# SAM_E54_Xplained_Pro_triple_input_power_.net
KiCad netlist of a schematic drawn in Altium Designer
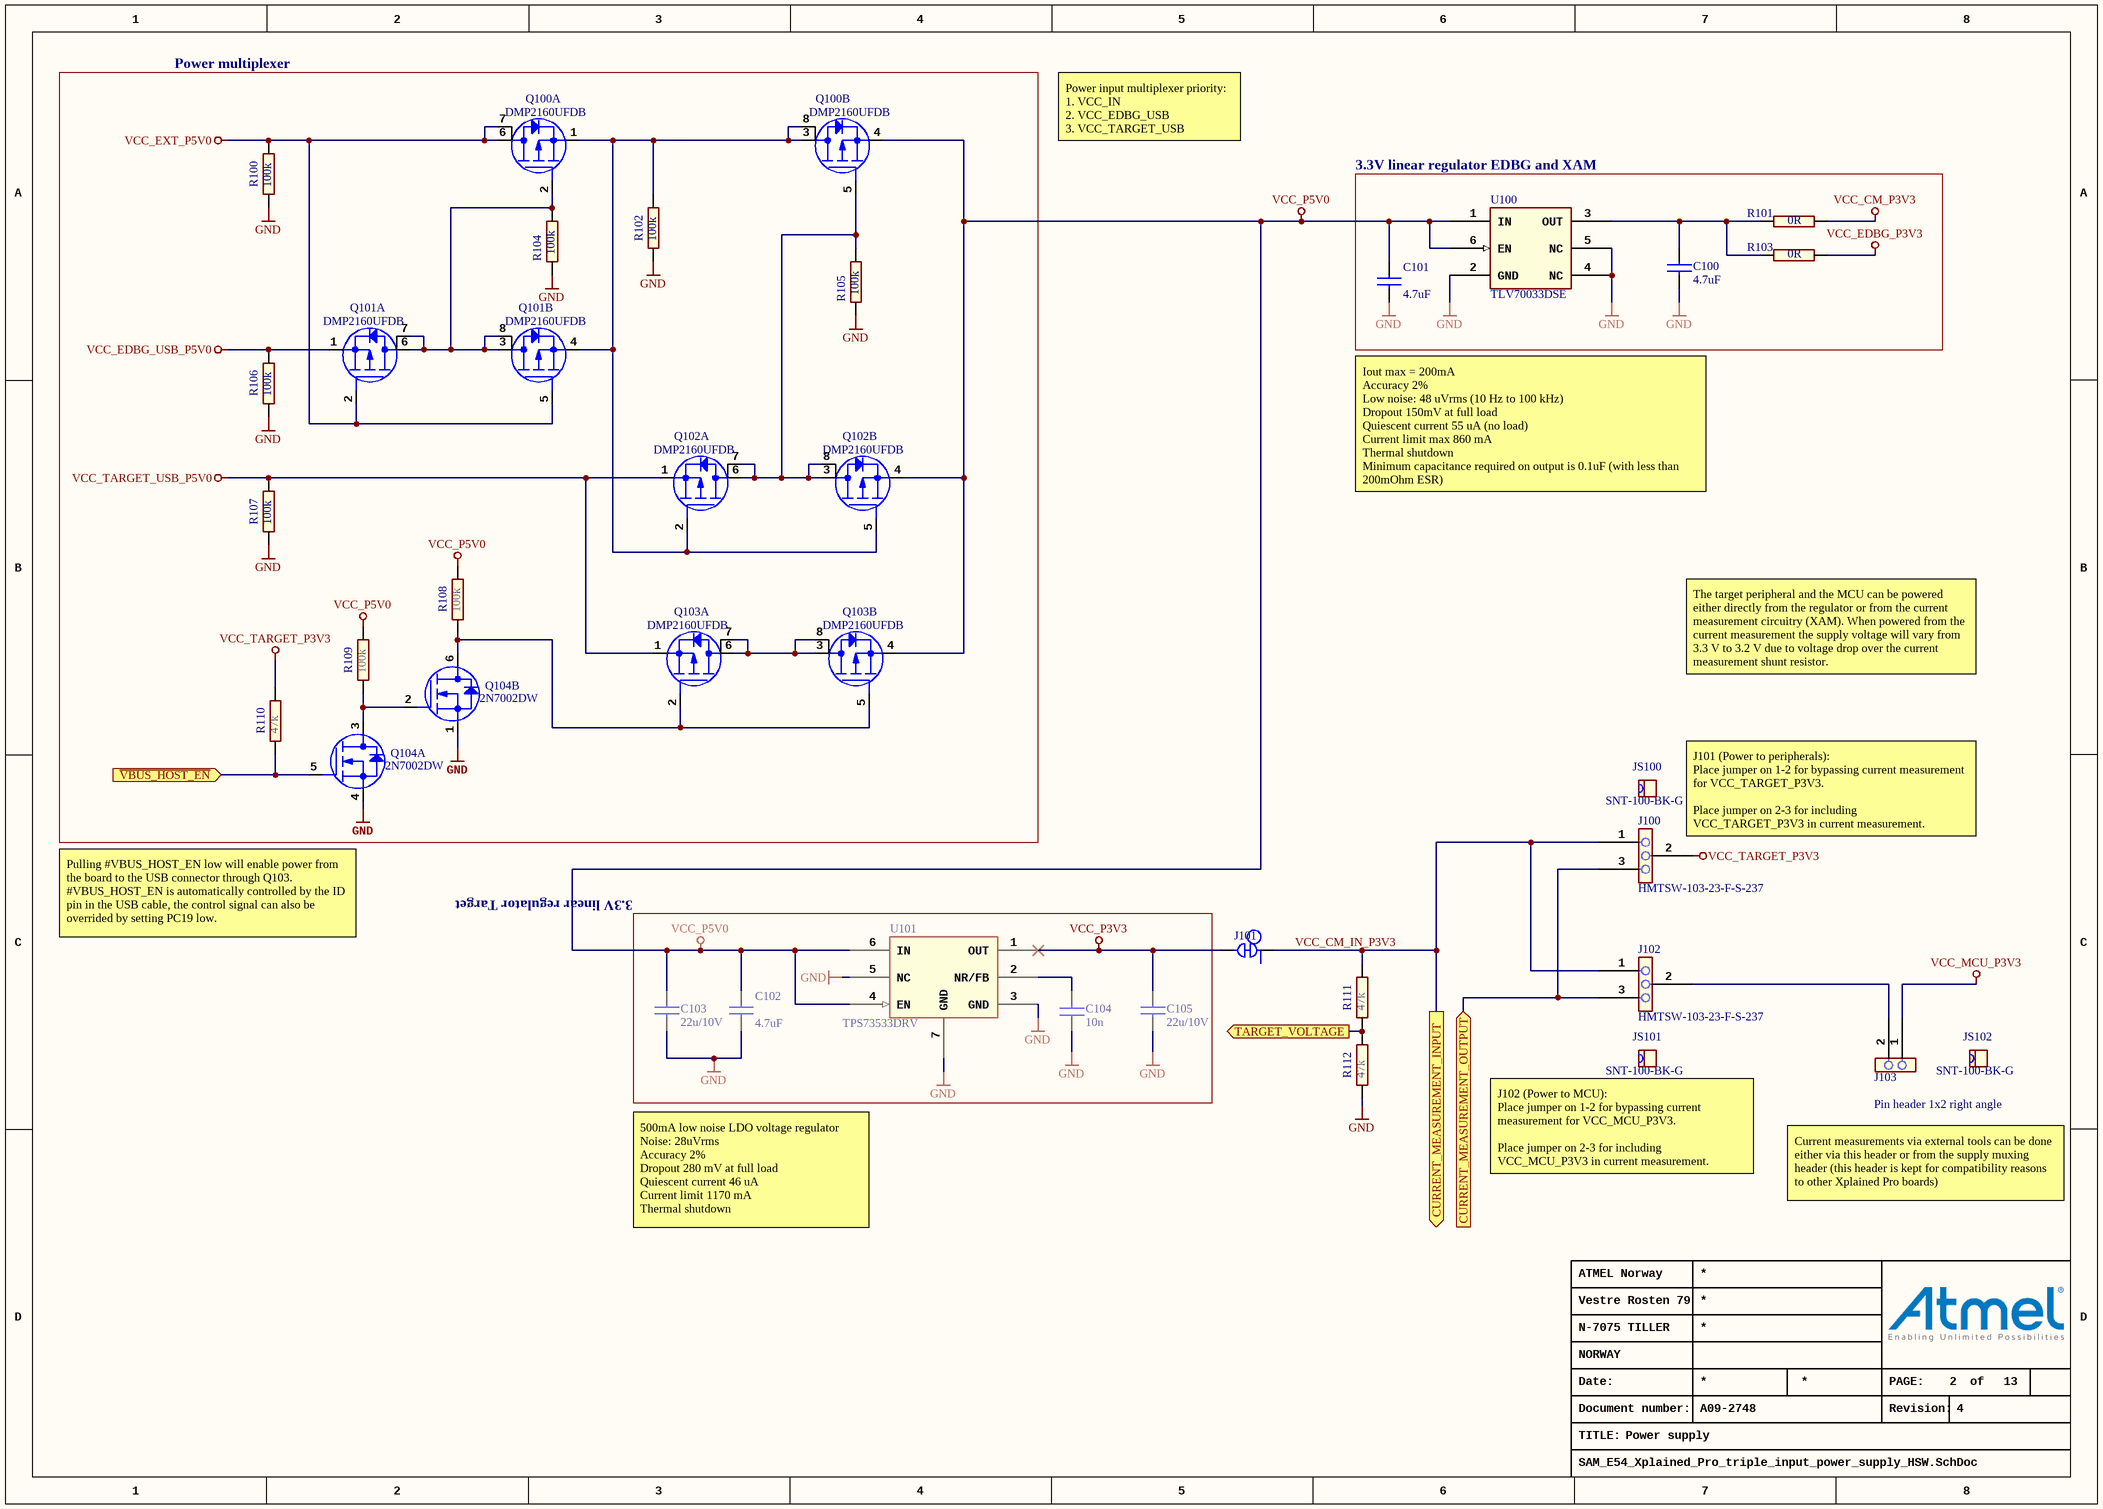
[diagram p0: SAM_E54_Xplained_Pro_triple_input_power_supply_HSW.SchDoc]

(export (version "E")
  (design (tool "Eeschema 10.0.6"))
  (components
    (comp (ref "C100")
      (value "4.7uF")
      (footprint "AP1-00117")
      (description "Ceramic capacitor, SMD 0603, X5R, 10V, 10% (de31036)")
      (fields (field (name "TOLERANCE") "10%") (field (name "MANUFACTURER") "WALSIN Technology Corporation"))
      (libsource (lib "AltiumDbLib") (part "CAP-NONPOL"))
    )
    (comp (ref "C101")
      (value "4.7uF")
      (footprint "AP1-00117")
      (description "Ceramic capacitor, SMD 0603, X5R, 10V, 10% (de31036)")
      (fields (field (name "TOLERANCE") "10%") (field (name "MANUFACTURER") "WALSIN Technology Corporation"))
      (libsource (lib "AltiumDbLib") (part "CAP-NONPOL"))
    )
    (comp (ref "C102")
      (value "4.7uF")
      (footprint "AP1-00117")
      (description "Ceramic capacitor, SMD 0603, X5R, 10V, 10% (de31036)")
      (fields (field (name "TOLERANCE") "10%") (field (name "MANUFACTURER") "WALSIN Technology Corporation"))
      (libsource (lib "AltiumDbLib") (part "CAP-NONPOL"))
    )
    (comp (ref "C103")
      (value "22u/10V")
      (footprint "AP1-00117")
      (description "Ceramic capacitor, SMD 0603, X5R,10V, Â±20%")
      (fields (field (name "MANUFACTURER") "Murata") (field (name "MPN") "GRM188R61A226ME15D"))
      (libsource (lib "AltiumDbLib") (part "CAP-NONPOL"))
    )
    (comp (ref "C104")
      (value "10n")
      (footprint "AP1-00053")
      (description "Ceramic capacitor, SMD 0402, X7R, 25V, +/-10%")
      (fields (field (name "TOLERANCE") "25V, +/-10%") (field (name "MANUFACTURER") "YAGEO CORP"))
      (libsource (lib "AltiumDbLib") (part "CAP-NONPOL"))
    )
    (comp (ref "C105")
      (value "22u/10V")
      (footprint "AP1-00117")
      (description "Ceramic capacitor, SMD 0603, X5R,10V, Â±20%")
      (fields (field (name "MANUFACTURER") "Murata") (field (name "MPN") "GRM188R61A226ME15D"))
      (libsource (lib "AltiumDbLib") (part "CAP-NONPOL"))
    )
    (comp (ref "J100")
      (value "HMTSW-103-23-F-S-237")
      (footprint "AP8-00745")
      (description "1x3 pin header, 2.54mm pitch, Pin-in-Paste THM, 1mm hole")
      (fields (field (name "MANUFACTURER") "SAMTEC"))
      (libsource (lib "AltiumDbLib") (part "HEADER 1x3"))
    )
    (comp (ref "J101")
      (value "~")
      (footprint "AP9-00044")
      (description "Default closed SMD strap, 0603 size")
      (libsource (lib "AltiumDbLib") (part "SMD-STRAP_CLOSED"))
    )
    (comp (ref "J102")
      (value "HMTSW-103-23-F-S-237")
      (footprint "AP8-00745")
      (description "1x3 pin header, 2.54mm pitch, Pin-in-Paste THM, 1mm hole")
      (fields (field (name "MANUFACTURER") "SAMTEC"))
      (libsource (lib "AltiumDbLib") (part "HEADER 1x3"))
    )
    (comp (ref "J103")
      (value "Pin header 1x2 right angle")
      (footprint "AP8-00367")
      (description "1x2 pin header, right angle, 2.54 mm pitch, through-hole")
      (fields (field (name "MANUFACTURER") "Pro-data International Corp") (field (name "MPN") "2213R-2G"))
      (libsource (lib "AltiumDbLib") (part "HEADER 1x2"))
    )
    (comp (ref "JS100")
      (value "SNT-100-BK-G")
      (footprint "AP8-00525")
      (description "Jumper cap for 2.54mm pinheader")
      (fields (field (name "MANUFACTURER") "SAMTEC"))
      (libsource (lib "AltiumDbLib") (part "JUMPER_CAP"))
    )
    (comp (ref "JS101")
      (value "SNT-100-BK-G")
      (footprint "AP8-00525")
      (description "Jumper cap for 2.54mm pinheader")
      (fields (field (name "MANUFACTURER") "SAMTEC"))
      (libsource (lib "AltiumDbLib") (part "JUMPER_CAP"))
    )
    (comp (ref "JS102")
      (value "SNT-100-BK-G")
      (footprint "AP8-00525")
      (description "Jumper cap for 2.54mm pinheader")
      (fields (field (name "MANUFACTURER") "SAMTEC"))
      (libsource (lib "AltiumDbLib") (part "JUMPER_CAP"))
    )
    (comp (ref "Q100")
      (value "DMP2160UFDB")
      (footprint "AP5-00047")
      (description "MOSFET 20V 3.8A DUAL P-CHAN, Rds 70 mOhms, Vgs 12V, Vds -20")
      (fields (field (name "MANUFACTURER") "Diodes Incorporated") (field (name "MPN") "DMP2160UFDB-7"))
      (libsource (lib "AltiumDbLib") (part "MOSFET_DUAL_P_S1G1D2S2G2D1D1D2"))
    )
    (comp (ref "Q101")
      (value "DMP2160UFDB")
      (footprint "AP5-00047")
      (description "MOSFET 20V 3.8A DUAL P-CHAN, Rds 70 mOhms, Vgs 12V, Vds -20")
      (fields (field (name "MANUFACTURER") "Diodes Incorporated") (field (name "MPN") "DMP2160UFDB-7"))
      (libsource (lib "AltiumDbLib") (part "MOSFET_DUAL_P_S1G1D2S2G2D1D1D2"))
    )
    (comp (ref "Q102")
      (value "DMP2160UFDB")
      (footprint "AP5-00047")
      (description "MOSFET 20V 3.8A DUAL P-CHAN, Rds 70 mOhms, Vgs 12V, Vds -20")
      (fields (field (name "MANUFACTURER") "Diodes Incorporated") (field (name "MPN") "DMP2160UFDB-7"))
      (libsource (lib "AltiumDbLib") (part "MOSFET_DUAL_P_S1G1D2S2G2D1D1D2"))
    )
    (comp (ref "Q103")
      (value "DMP2160UFDB")
      (footprint "AP5-00047")
      (description "MOSFET 20V 3.8A DUAL P-CHAN, Rds 70 mOhms, Vgs 12V, Vds -20")
      (fields (field (name "MANUFACTURER") "Diodes Incorporated") (field (name "MPN") "DMP2160UFDB-7"))
      (libsource (lib "AltiumDbLib") (part "MOSFET_DUAL_P_S1G1D2S2G2D1D1D2"))
    )
    (comp (ref "Q104")
      (value "2N7002DW")
      (footprint "AP5-00001")
      (description "Dual N-Channel MOSFET, 60V, 115mA cont,RDS(ON) < 7.5 Ohm @50mA@5V, SOT-363")
      (fields
        (field (name "MANUFACTURER") "Fairchild")
        (field (name "Comment") "Same as 2N7002 but with two MOSFETs in one package")
      )
      (libsource (lib "AltiumDbLib") (part "MOSFET_DUAL_N_S2G2D1S1G1D2"))
    )
    (comp (ref "R100")
      (value "100k")
      (footprint "AP2-00011")
      (description "Thick film resistor, SMD 0402, 1/16W, 1%")
      (fields (field (name "TOLERANCE") "1 %") (field (name "MANUFACTURER") "ASJ"))
      (libsource (lib "") (part "R2_1"))
    )
    (comp (ref "R101")
      (value "0R")
      (footprint "AP2-00011")
      (description "RES 0.0 OHM 1/16W 0402 SMD")
      (fields (field (name "TOLERANCE") "1 %") (field (name "MANUFACTURER") "(n/a)"))
      (libsource (lib "") (part "R2_3"))
    )
    (comp (ref "R102")
      (value "100k")
      (footprint "AP2-00011")
      (description "Thick film resistor, SMD 0402, 1/16W, 1%")
      (fields (field (name "TOLERANCE") "1 %") (field (name "MANUFACTURER") "ASJ"))
      (libsource (lib "") (part "R2_1"))
    )
    (comp (ref "R103")
      (value "0R")
      (footprint "AP2-00011")
      (description "RES 0.0 OHM 1/16W 0402 SMD")
      (fields (field (name "TOLERANCE") "1 %") (field (name "MANUFACTURER") "(n/a)"))
      (libsource (lib "") (part "R2_3"))
    )
    (comp (ref "R104")
      (value "100k")
      (footprint "AP2-00011")
      (description "Thick film resistor, SMD 0402, 1/16W, 1%")
      (fields (field (name "TOLERANCE") "1 %") (field (name "MANUFACTURER") "ASJ"))
      (libsource (lib "") (part "R2_2"))
    )
    (comp (ref "R105")
      (value "100k")
      (footprint "AP2-00011")
      (description "Thick film resistor, SMD 0402, 1/16W, 1%")
      (fields (field (name "TOLERANCE") "1 %") (field (name "MANUFACTURER") "ASJ"))
      (libsource (lib "") (part "R2_1"))
    )
    (comp (ref "R106")
      (value "100k")
      (footprint "AP2-00011")
      (description "Thick film resistor, SMD 0402, 1/16W, 1%")
      (fields (field (name "TOLERANCE") "1 %") (field (name "MANUFACTURER") "ASJ"))
      (libsource (lib "") (part "R2_1"))
    )
    (comp (ref "R107")
      (value "100k")
      (footprint "AP2-00011")
      (description "Thick film resistor, SMD 0402, 1/16W, 1%")
      (fields (field (name "TOLERANCE") "1 %") (field (name "MANUFACTURER") "ASJ"))
      (libsource (lib "") (part "R2_1"))
    )
    (comp (ref "R108")
      (value "100k")
      (footprint "AP2-00011")
      (description "Thick film resistor, SMD 0402, 1/16W, 1%")
      (fields (field (name "TOLERANCE") "1 %") (field (name "MANUFACTURER") "ASJ"))
      (libsource (lib "") (part "R2_1"))
    )
    (comp (ref "R109")
      (value "100k")
      (footprint "AP2-00011")
      (description "Thick film resistor, SMD 0402, 1/16W, 1%")
      (fields (field (name "TOLERANCE") "1 %") (field (name "MANUFACTURER") "ASJ"))
      (libsource (lib "") (part "R2_1"))
    )
    (comp (ref "R110")
      (value "47k")
      (footprint "AP2-00011")
      (description "Thick film resistor, SMD 0402, 1/16W, 1%")
      (fields (field (name "TOLERANCE") "1 %") (field (name "MANUFACTURER") "KOA"))
      (libsource (lib "AltiumDbLib") (part "R2"))
    )
    (comp (ref "R111")
      (value "47k")
      (footprint "AP2-00011")
      (description "Thick film resistor, SMD 0402, 1/16W, 1%")
      (fields (field (name "TOLERANCE") "1 %") (field (name "MANUFACTURER") "KOA"))
      (libsource (lib "AltiumDbLib") (part "R2"))
    )
    (comp (ref "R112")
      (value "47k")
      (footprint "AP2-00011")
      (description "Thick film resistor, SMD 0402, 1/16W, 1%")
      (fields (field (name "TOLERANCE") "1 %") (field (name "MANUFACTURER") "KOA"))
      (libsource (lib "AltiumDbLib") (part "R2"))
    )
    (comp (ref "U100")
      (value "TLV70033DSE")
      (footprint "AP6-00262")
      (description "LDO, 200 mA, Iq=31 uA, Vdo=250mV, Vout=3.3V, VIN= 2 V to 5.5V, SON-6 package")
      (fields (field (name "MANUFACTURER") "Texas Instruments"))
      (libsource (lib "AltiumDbLib") (part "TLV70033"))
    )
    (comp (ref "U101")
      (value "TPS73533DRV")
      (footprint "AP6-00162")
      (fields (field (name "MANUFACTURER") "Texas Instruments"))
      (libsource (lib "AltiumDbLib") (part "TPS735xxDRV"))
    )
  )
  (nets
    (net (code "1") (name "/CURRENT_MEASUREMENT_OUTPUT") (class "Default")
      (node (ref "J100") (pin "3") (pinfunction "3_3") (pintype "passive"))
      (node (ref "J102") (pin "3") (pinfunction "3_3") (pintype "passive"))
    )
    (net (code "2") (name "/TARGET_VOLTAGE") (class "Default")
      (node (ref "R111") (pin "1") (pinfunction "1_1") (pintype "passive"))
      (node (ref "R112") (pin "2") (pinfunction "2_2") (pintype "passive"))
    )
    (net (code "3") (name "/VCC_CM_IN_P3V3") (class "Default")
      (node (ref "J100") (pin "1") (pinfunction "1_1") (pintype "passive"))
      (node (ref "J101") (pin "1") (pinfunction "1_1") (pintype "passive"))
      (node (ref "J102") (pin "1") (pinfunction "1_1") (pintype "passive"))
      (node (ref "R111") (pin "2") (pinfunction "2_2") (pintype "passive"))
    )
    (net (code "4") (name "/~{VBUS_HOST_EN}") (class "Default")
      (node (ref "Q104") (pin "5") (pinfunction "G1_5") (pintype "passive"))
      (node (ref "R110") (pin "1") (pinfunction "1_1") (pintype "passive"))
    )
    (net (code "5") (name "GND") (class "Default")
      (node (ref "C100") (pin "2") (pinfunction "2_2") (pintype "passive"))
      (node (ref "C101") (pin "2") (pinfunction "2_2") (pintype "passive"))
      (node (ref "C102") (pin "2") (pinfunction "2_2") (pintype "passive"))
      (node (ref "C103") (pin "2") (pinfunction "2_2") (pintype "passive"))
      (node (ref "C104") (pin "1") (pinfunction "1_1") (pintype "passive"))
      (node (ref "C105") (pin "2") (pinfunction "2_2") (pintype "passive"))
      (node (ref "Q104") (pin "1") (pinfunction "S2_1") (pintype "passive"))
      (node (ref "Q104") (pin "4") (pinfunction "S1_4") (pintype "passive"))
      (node (ref "R100") (pin "1") (pinfunction "1_1") (pintype "passive"))
      (node (ref "R102") (pin "1") (pinfunction "1_1") (pintype "passive"))
      (node (ref "R104") (pin "2") (pinfunction "2_2") (pintype "passive"))
      (node (ref "R105") (pin "1") (pinfunction "1_1") (pintype "passive"))
      (node (ref "R106") (pin "1") (pinfunction "1_1") (pintype "passive"))
      (node (ref "R107") (pin "1") (pinfunction "1_1") (pintype "passive"))
      (node (ref "R112") (pin "1") (pinfunction "1_1") (pintype "passive"))
      (node (ref "U100") (pin "2") (pinfunction "GND_2") (pintype "power_in"))
      (node (ref "U100") (pin "4") (pinfunction "NC_4") (pintype "passive"))
      (node (ref "U100") (pin "5") (pinfunction "NC_5") (pintype "passive"))
      (node (ref "U101") (pin "3") (pinfunction "GND_3") (pintype "power_in"))
      (node (ref "U101") (pin "5") (pinfunction "NC_5") (pintype "passive"))
      (node (ref "U101") (pin "7") (pinfunction "GND_7") (pintype "power_in"))
    )
    (net (code "6") (name "Net-(J102-Pad2)") (class "Default")
      (node (ref "J102") (pin "2") (pinfunction "2_2") (pintype "passive"))
      (node (ref "J103") (pin "2") (pinfunction "2_2") (pintype "passive"))
    )
    (net (code "7") (name "Net-(Q100A-G1)") (class "Default")
      (node (ref "Q100") (pin "2") (pinfunction "G1_2") (pintype "passive"))
      (node (ref "Q101") (pin "3") (pinfunction "D2_3") (pintype "passive"))
      (node (ref "Q101") (pin "6") (pinfunction "D1_6") (pintype "passive"))
      (node (ref "Q101") (pin "7") (pinfunction "D1_PAD_7") (pintype "passive"))
      (node (ref "Q101") (pin "8") (pinfunction "D2_PAD_8") (pintype "passive"))
      (node (ref "R104") (pin "1") (pinfunction "1_1") (pintype "passive"))
    )
    (net (code "8") (name "Net-(Q100A-S1)") (class "Default")
      (node (ref "Q100") (pin "1") (pinfunction "S1_1") (pintype "passive"))
      (node (ref "Q100") (pin "3") (pinfunction "D2_3") (pintype "passive"))
      (node (ref "Q100") (pin "8") (pinfunction "D2_PAD_8") (pintype "passive"))
      (node (ref "Q101") (pin "4") (pinfunction "S2_4") (pintype "passive"))
      (node (ref "Q102") (pin "2") (pinfunction "G1_2") (pintype "passive"))
      (node (ref "Q102") (pin "5") (pinfunction "G2_5") (pintype "passive"))
      (node (ref "R102") (pin "2") (pinfunction "2_2") (pintype "passive"))
    )
    (net (code "9") (name "Net-(Q100B-G2)") (class "Default")
      (node (ref "Q100") (pin "5") (pinfunction "G2_5") (pintype "passive"))
      (node (ref "Q102") (pin "3") (pinfunction "D2_3") (pintype "passive"))
      (node (ref "Q102") (pin "6") (pinfunction "D1_6") (pintype "passive"))
      (node (ref "Q102") (pin "7") (pinfunction "D1_PAD_7") (pintype "passive"))
      (node (ref "Q102") (pin "8") (pinfunction "D2_PAD_8") (pintype "passive"))
      (node (ref "R105") (pin "2") (pinfunction "2_2") (pintype "passive"))
    )
    (net (code "10") (name "Net-(Q103A-D1)") (class "Default")
      (node (ref "Q103") (pin "3") (pinfunction "D2_3") (pintype "passive"))
      (node (ref "Q103") (pin "6") (pinfunction "D1_6") (pintype "passive"))
      (node (ref "Q103") (pin "7") (pinfunction "D1_PAD_7") (pintype "passive"))
      (node (ref "Q103") (pin "8") (pinfunction "D2_PAD_8") (pintype "passive"))
    )
    (net (code "11") (name "Net-(Q103A-G1)") (class "Default")
      (node (ref "Q103") (pin "2") (pinfunction "G1_2") (pintype "passive"))
      (node (ref "Q103") (pin "5") (pinfunction "G2_5") (pintype "passive"))
      (node (ref "Q104") (pin "6") (pinfunction "D2_6") (pintype "passive"))
      (node (ref "R108") (pin "1") (pinfunction "1_1") (pintype "passive"))
    )
    (net (code "12") (name "Net-(Q104A-D1)") (class "Default")
      (node (ref "Q104") (pin "2") (pinfunction "G2_2") (pintype "passive"))
      (node (ref "Q104") (pin "3") (pinfunction "D1_3") (pintype "passive"))
      (node (ref "R109") (pin "1") (pinfunction "1_1") (pintype "passive"))
    )
    (net (code "13") (name "Net-(U100-OUT)") (class "Default")
      (node (ref "C100") (pin "1") (pinfunction "1_1") (pintype "passive"))
      (node (ref "R101") (pin "2") (pinfunction "2_2") (pintype "passive"))
      (node (ref "R103") (pin "2") (pinfunction "2_2") (pintype "passive"))
      (node (ref "U100") (pin "3") (pinfunction "OUT_3") (pintype "power_in"))
    )
    (net (code "14") (name "Net-(U101-NR{slash}FB)") (class "Default")
      (node (ref "C104") (pin "2") (pinfunction "2_2") (pintype "passive"))
      (node (ref "U101") (pin "2") (pinfunction "NR/FB_2") (pintype "passive"))
    )
    (net (code "15") (name "VCC_CM_P3V3") (class "Default")
      (node (ref "R101") (pin "1") (pinfunction "1_1") (pintype "passive"))
    )
    (net (code "16") (name "VCC_EDBG_P3V3") (class "Default")
      (node (ref "R103") (pin "1") (pinfunction "1_1") (pintype "passive"))
    )
    (net (code "17") (name "VCC_EDBG_USB_P5V0") (class "Default")
      (node (ref "Q101") (pin "1") (pinfunction "S1_1") (pintype "passive"))
      (node (ref "R106") (pin "2") (pinfunction "2_2") (pintype "passive"))
    )
    (net (code "18") (name "VCC_EXT_P5V0") (class "Default")
      (node (ref "Q100") (pin "6") (pinfunction "D1_6") (pintype "passive"))
      (node (ref "Q100") (pin "7") (pinfunction "D1_PAD_7") (pintype "passive"))
      (node (ref "Q101") (pin "2") (pinfunction "G1_2") (pintype "passive"))
      (node (ref "Q101") (pin "5") (pinfunction "G2_5") (pintype "passive"))
      (node (ref "R100") (pin "2") (pinfunction "2_2") (pintype "passive"))
    )
    (net (code "19") (name "VCC_MCU_P3V3") (class "Default")
      (node (ref "J103") (pin "1") (pinfunction "1_1") (pintype "passive"))
    )
    (net (code "20") (name "VCC_P3V3") (class "Default")
      (node (ref "C105") (pin "1") (pinfunction "1_1") (pintype "passive"))
      (node (ref "J101") (pin "2") (pinfunction "2_2") (pintype "passive"))
      (node (ref "U101") (pin "1") (pinfunction "OUT_1") (pintype "power_in"))
    )
    (net (code "21") (name "VCC_P5V0") (class "Default")
      (node (ref "C101") (pin "1") (pinfunction "1_1") (pintype "passive"))
      (node (ref "C102") (pin "1") (pinfunction "1_1") (pintype "passive"))
      (node (ref "C103") (pin "1") (pinfunction "1_1") (pintype "passive"))
      (node (ref "Q100") (pin "4") (pinfunction "S2_4") (pintype "passive"))
      (node (ref "Q102") (pin "4") (pinfunction "S2_4") (pintype "passive"))
      (node (ref "Q103") (pin "4") (pinfunction "S2_4") (pintype "passive"))
      (node (ref "R108") (pin "2") (pinfunction "2_2") (pintype "passive"))
      (node (ref "R109") (pin "2") (pinfunction "2_2") (pintype "passive"))
      (node (ref "U100") (pin "1") (pinfunction "IN_1") (pintype "power_in"))
      (node (ref "U100") (pin "6") (pinfunction "EN_6") (pintype "input"))
      (node (ref "U101") (pin "4") (pinfunction "EN_4") (pintype "input"))
      (node (ref "U101") (pin "6") (pinfunction "IN_6") (pintype "power_in"))
    )
    (net (code "22") (name "VCC_TARGET_P3V3") (class "Default")
      (node (ref "J100") (pin "2") (pinfunction "2_2") (pintype "passive"))
      (node (ref "R110") (pin "2") (pinfunction "2_2") (pintype "passive"))
    )
    (net (code "23") (name "VCC_TARGET_USB_P5V0") (class "Default")
      (node (ref "Q102") (pin "1") (pinfunction "S1_1") (pintype "passive"))
      (node (ref "Q103") (pin "1") (pinfunction "S1_1") (pintype "passive"))
      (node (ref "R107") (pin "2") (pinfunction "2_2") (pintype "passive"))
    )
  )
)
